# EasyEDA_Schema_SourceFile.net
KiCad netlist of a schematic drawn in EasyEDA
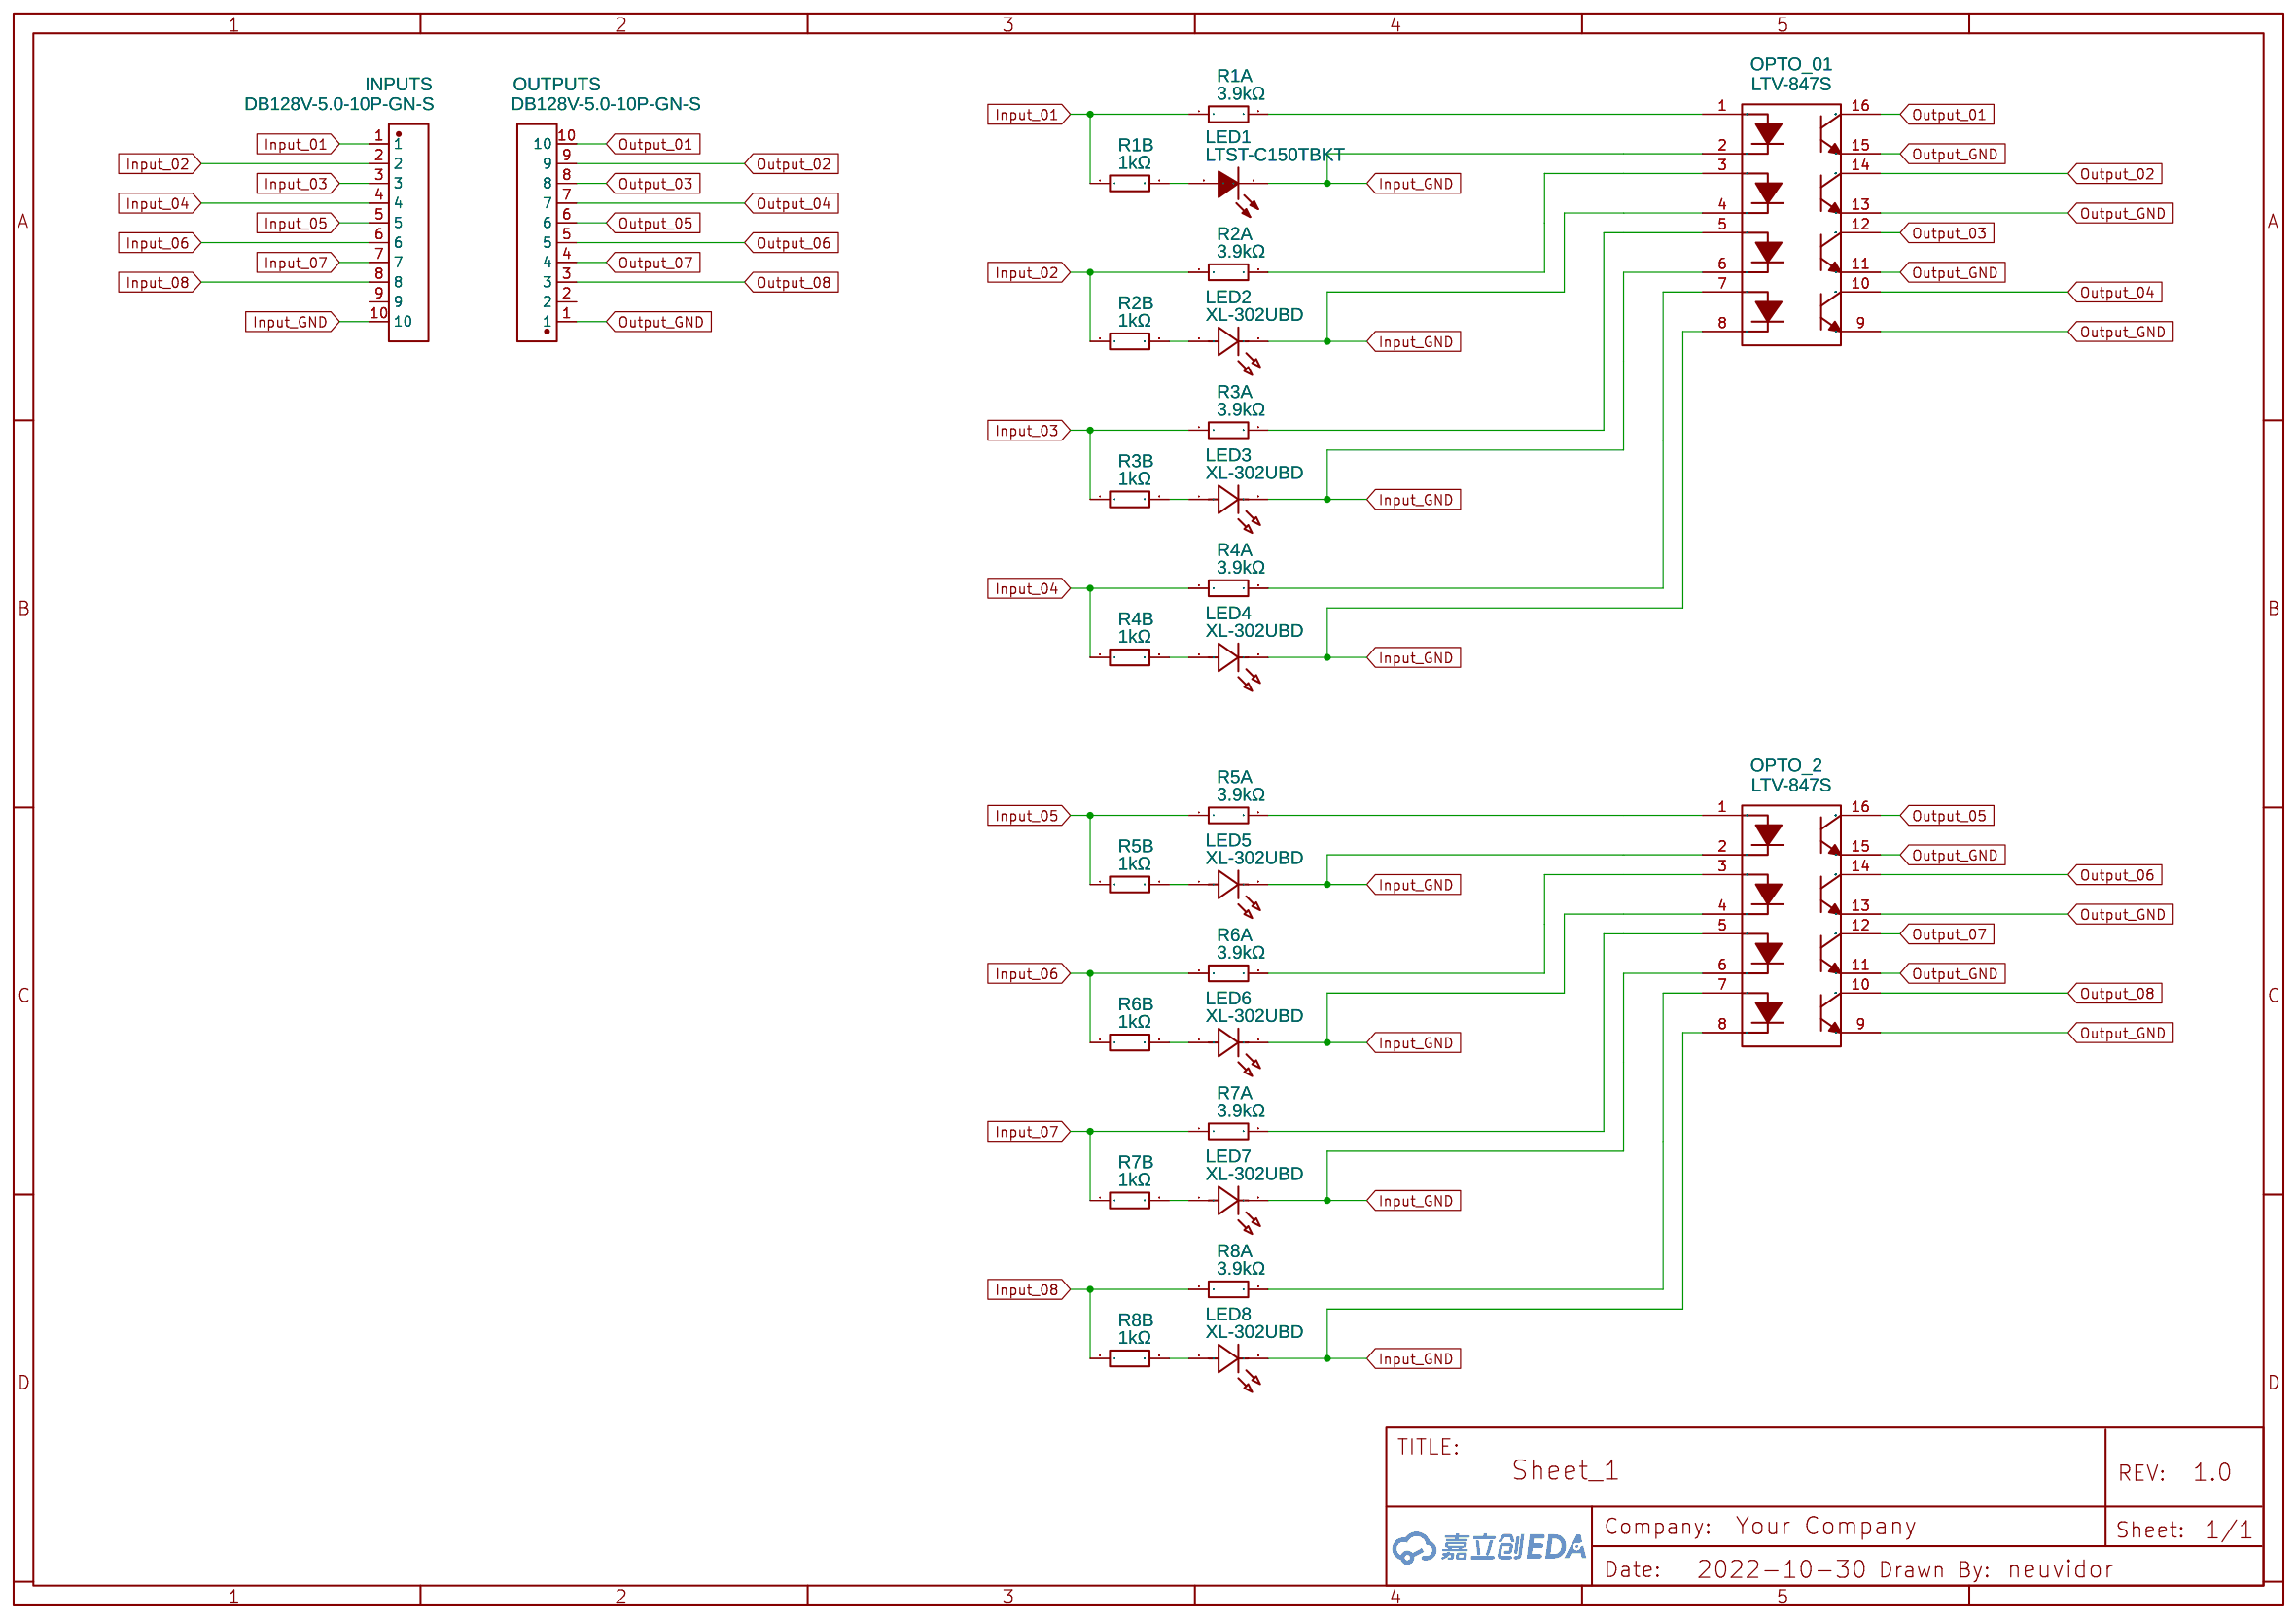
[diagram p0: schematic sheet]

(export (version "E")
  (design (tool "Eeschema 10.0.6"))
  (components
    (comp (ref "INPUTS")
      (value "DB128V-5.0-10P-GN-S")
      (fields (field (name "BOM_Supplier Part") "C725714"))
      (libsource (lib "") (part "DB128V-5.0-10P-GN-S_1"))
    )
    (comp (ref "LED1")
      (value "LTST-C150TBKT")
      (fields (field (name "BOM_Supplier Part") "C125088"))
      (libsource (lib "") (part "LTST-C150TBKT"))
    )
    (comp (ref "LED2")
      (value "XL-302UBD")
      (fields (field (name "BOM_Supplier Part") "C2895474"))
      (libsource (lib "") (part "XL-302UBD"))
    )
    (comp (ref "LED3")
      (value "XL-302UBD")
      (fields (field (name "BOM_Supplier Part") "C2895474"))
      (libsource (lib "") (part "XL-302UBD"))
    )
    (comp (ref "LED4")
      (value "XL-302UBD")
      (fields (field (name "BOM_Supplier Part") "C2895474"))
      (libsource (lib "") (part "XL-302UBD"))
    )
    (comp (ref "LED5")
      (value "XL-302UBD")
      (fields (field (name "BOM_Supplier Part") "C2895474"))
      (libsource (lib "") (part "XL-302UBD"))
    )
    (comp (ref "LED6")
      (value "XL-302UBD")
      (fields (field (name "BOM_Supplier Part") "C2895474"))
      (libsource (lib "") (part "XL-302UBD"))
    )
    (comp (ref "LED7")
      (value "XL-302UBD")
      (fields (field (name "BOM_Supplier Part") "C2895474"))
      (libsource (lib "") (part "XL-302UBD"))
    )
    (comp (ref "LED8")
      (value "XL-302UBD")
      (fields (field (name "BOM_Supplier Part") "C2895474"))
      (libsource (lib "") (part "XL-302UBD"))
    )
    (comp (ref "OPTO_01")
      (value "LTV-847S")
      (fields (field (name "BOM_Supplier Part") "C114599"))
      (libsource (lib "") (part "LTV-847S"))
    )
    (comp (ref "OPTO_2")
      (value "LTV-847S")
      (fields (field (name "BOM_Supplier Part") "C114599"))
      (libsource (lib "") (part "LTV-847S"))
    )
    (comp (ref "OUTPUTS")
      (value "DB128V-5.0-10P-GN-S")
      (fields (field (name "BOM_Supplier Part") "C725714"))
      (libsource (lib "") (part "DB128V-5.0-10P-GN-S"))
    )
    (comp (ref "R1A")
      (value "3.9kΩ")
      (fields
        (field (name "BOM_Manufacturer Part") "AECR1206F3K90K9")
        (field (name "BOM_Supplier Part") "C352079")
      )
      (libsource (lib "") (part "AECR1206F3K90K9_3"))
    )
    (comp (ref "R1B")
      (value "1kΩ")
      (fields
        (field (name "BOM_Manufacturer Part") "PTFR1206B1K00P9")
        (field (name "BOM_Supplier Part") "C351483")
      )
      (libsource (lib "") (part "PTFR1206B1K00P9_1"))
    )
    (comp (ref "R2A")
      (value "3.9kΩ")
      (fields
        (field (name "BOM_Manufacturer Part") "AECR1206F3K90K9")
        (field (name "BOM_Supplier Part") "C352079")
      )
      (libsource (lib "") (part "AECR1206F3K90K9_5"))
    )
    (comp (ref "R2B")
      (value "1kΩ")
      (fields
        (field (name "BOM_Manufacturer Part") "PTFR1206B1K00P9")
        (field (name "BOM_Supplier Part") "C351483")
      )
      (libsource (lib "") (part "PTFR1206B1K00P9_2"))
    )
    (comp (ref "R3A")
      (value "3.9kΩ")
      (fields
        (field (name "BOM_Manufacturer Part") "AECR1206F3K90K9")
        (field (name "BOM_Supplier Part") "C352079")
      )
      (libsource (lib "") (part "AECR1206F3K90K9_2"))
    )
    (comp (ref "R3B")
      (value "1kΩ")
      (fields
        (field (name "BOM_Manufacturer Part") "PTFR1206B1K00P9")
        (field (name "BOM_Supplier Part") "C351483")
      )
      (libsource (lib "") (part "PTFR1206B1K00P9_6"))
    )
    (comp (ref "R4A")
      (value "3.9kΩ")
      (fields
        (field (name "BOM_Manufacturer Part") "AECR1206F3K90K9")
        (field (name "BOM_Supplier Part") "C352079")
      )
      (libsource (lib "") (part "AECR1206F3K90K9"))
    )
    (comp (ref "R4B")
      (value "1kΩ")
      (fields
        (field (name "BOM_Manufacturer Part") "PTFR1206B1K00P9")
        (field (name "BOM_Supplier Part") "C351483")
      )
      (libsource (lib "") (part "PTFR1206B1K00P9_5"))
    )
    (comp (ref "R5A")
      (value "3.9kΩ")
      (fields
        (field (name "BOM_Manufacturer Part") "AECR1206F3K90K9")
        (field (name "BOM_Supplier Part") "C352079")
      )
      (libsource (lib "") (part "AECR1206F3K90K9_7"))
    )
    (comp (ref "R5B")
      (value "1kΩ")
      (fields
        (field (name "BOM_Manufacturer Part") "PTFR1206B1K00P9")
        (field (name "BOM_Supplier Part") "C351483")
      )
      (libsource (lib "") (part "PTFR1206B1K00P9_3"))
    )
    (comp (ref "R6A")
      (value "3.9kΩ")
      (fields
        (field (name "BOM_Manufacturer Part") "AECR1206F3K90K9")
        (field (name "BOM_Supplier Part") "C352079")
      )
      (libsource (lib "") (part "AECR1206F3K90K9_1"))
    )
    (comp (ref "R6B")
      (value "1kΩ")
      (fields
        (field (name "BOM_Manufacturer Part") "PTFR1206B1K00P9")
        (field (name "BOM_Supplier Part") "C351483")
      )
      (libsource (lib "") (part "PTFR1206B1K00P9_7"))
    )
    (comp (ref "R7A")
      (value "3.9kΩ")
      (fields
        (field (name "BOM_Manufacturer Part") "AECR1206F3K90K9")
        (field (name "BOM_Supplier Part") "C352079")
      )
      (libsource (lib "") (part "AECR1206F3K90K9_4"))
    )
    (comp (ref "R7B")
      (value "1kΩ")
      (fields
        (field (name "BOM_Manufacturer Part") "PTFR1206B1K00P9")
        (field (name "BOM_Supplier Part") "C351483")
      )
      (libsource (lib "") (part "PTFR1206B1K00P9"))
    )
    (comp (ref "R8A")
      (value "3.9kΩ")
      (fields
        (field (name "BOM_Manufacturer Part") "AECR1206F3K90K9")
        (field (name "BOM_Supplier Part") "C352079")
      )
      (libsource (lib "") (part "AECR1206F3K90K9_6"))
    )
    (comp (ref "R8B")
      (value "1kΩ")
      (fields
        (field (name "BOM_Manufacturer Part") "PTFR1206B1K00P9")
        (field (name "BOM_Supplier Part") "C351483")
      )
      (libsource (lib "") (part "PTFR1206B1K00P9_4"))
    )
  )
  (nets
    (net (code "1") (name "Input_01") (class "Default")
      (node (ref "INPUTS") (pin "1") (pinfunction "1_1") (pintype "unspecified"))
      (node (ref "R1A") (pin "1") (pinfunction "1_1") (pintype "unspecified"))
      (node (ref "R1B") (pin "1") (pinfunction "1_1") (pintype "unspecified"))
    )
    (net (code "2") (name "Input_02") (class "Default")
      (node (ref "INPUTS") (pin "2") (pinfunction "2_2") (pintype "unspecified"))
      (node (ref "R2A") (pin "1") (pinfunction "1_1") (pintype "unspecified"))
      (node (ref "R2B") (pin "1") (pinfunction "1_1") (pintype "unspecified"))
    )
    (net (code "3") (name "Input_03") (class "Default")
      (node (ref "INPUTS") (pin "3") (pinfunction "3_3") (pintype "unspecified"))
      (node (ref "R3A") (pin "1") (pinfunction "1_1") (pintype "unspecified"))
      (node (ref "R3B") (pin "1") (pinfunction "1_1") (pintype "unspecified"))
    )
    (net (code "4") (name "Input_04") (class "Default")
      (node (ref "INPUTS") (pin "4") (pinfunction "4_4") (pintype "unspecified"))
      (node (ref "R4A") (pin "1") (pinfunction "1_1") (pintype "unspecified"))
      (node (ref "R4B") (pin "1") (pinfunction "1_1") (pintype "unspecified"))
    )
    (net (code "5") (name "Input_05") (class "Default")
      (node (ref "INPUTS") (pin "5") (pinfunction "5_5") (pintype "unspecified"))
      (node (ref "R5A") (pin "1") (pinfunction "1_1") (pintype "unspecified"))
      (node (ref "R5B") (pin "1") (pinfunction "1_1") (pintype "unspecified"))
    )
    (net (code "6") (name "Input_06") (class "Default")
      (node (ref "INPUTS") (pin "6") (pinfunction "6_6") (pintype "unspecified"))
      (node (ref "R6A") (pin "1") (pinfunction "1_1") (pintype "unspecified"))
      (node (ref "R6B") (pin "1") (pinfunction "1_1") (pintype "unspecified"))
    )
    (net (code "7") (name "Input_07") (class "Default")
      (node (ref "INPUTS") (pin "7") (pinfunction "7_7") (pintype "unspecified"))
      (node (ref "R7A") (pin "1") (pinfunction "1_1") (pintype "unspecified"))
      (node (ref "R7B") (pin "1") (pinfunction "1_1") (pintype "unspecified"))
    )
    (net (code "8") (name "Input_08") (class "Default")
      (node (ref "INPUTS") (pin "8") (pinfunction "8_8") (pintype "unspecified"))
      (node (ref "R8A") (pin "1") (pinfunction "1_1") (pintype "unspecified"))
      (node (ref "R8B") (pin "1") (pinfunction "1_1") (pintype "unspecified"))
    )
    (net (code "9") (name "Input_GND") (class "Default")
      (node (ref "INPUTS") (pin "10") (pinfunction "10_10") (pintype "unspecified"))
      (node (ref "LED1") (pin "1") (pinfunction "K_1") (pintype "unspecified"))
      (node (ref "LED2") (pin "2") (pinfunction "A_2") (pintype "unspecified"))
      (node (ref "LED3") (pin "2") (pinfunction "A_2") (pintype "unspecified"))
      (node (ref "LED4") (pin "2") (pinfunction "A_2") (pintype "unspecified"))
      (node (ref "LED5") (pin "2") (pinfunction "A_2") (pintype "unspecified"))
      (node (ref "LED6") (pin "2") (pinfunction "A_2") (pintype "unspecified"))
      (node (ref "LED7") (pin "2") (pinfunction "A_2") (pintype "unspecified"))
      (node (ref "LED8") (pin "2") (pinfunction "A_2") (pintype "unspecified"))
      (node (ref "OPTO_01") (pin "2") (pinfunction "CAT1_2") (pintype "unspecified"))
      (node (ref "OPTO_01") (pin "4") (pinfunction "CAT2_4") (pintype "unspecified"))
      (node (ref "OPTO_01") (pin "6") (pinfunction "CAT3_6") (pintype "unspecified"))
      (node (ref "OPTO_01") (pin "8") (pinfunction "CAT4_8") (pintype "unspecified"))
      (node (ref "OPTO_2") (pin "2") (pinfunction "CAT1_2") (pintype "unspecified"))
      (node (ref "OPTO_2") (pin "4") (pinfunction "CAT2_4") (pintype "unspecified"))
      (node (ref "OPTO_2") (pin "6") (pinfunction "CAT3_6") (pintype "unspecified"))
      (node (ref "OPTO_2") (pin "8") (pinfunction "CAT4_8") (pintype "unspecified"))
    )
    (net (code "10") (name "Net-(LED1-A)") (class "Default")
      (node (ref "LED1") (pin "2") (pinfunction "A_2") (pintype "unspecified"))
      (node (ref "R1B") (pin "2") (pinfunction "2_2") (pintype "unspecified"))
    )
    (net (code "11") (name "Net-(LED2-K)") (class "Default")
      (node (ref "LED2") (pin "1") (pinfunction "K_1") (pintype "unspecified"))
      (node (ref "R2B") (pin "2") (pinfunction "2_2") (pintype "unspecified"))
    )
    (net (code "12") (name "Net-(LED3-K)") (class "Default")
      (node (ref "LED3") (pin "1") (pinfunction "K_1") (pintype "unspecified"))
      (node (ref "R3B") (pin "2") (pinfunction "2_2") (pintype "unspecified"))
    )
    (net (code "13") (name "Net-(LED4-K)") (class "Default")
      (node (ref "LED4") (pin "1") (pinfunction "K_1") (pintype "unspecified"))
      (node (ref "R4B") (pin "2") (pinfunction "2_2") (pintype "unspecified"))
    )
    (net (code "14") (name "Net-(LED5-K)") (class "Default")
      (node (ref "LED5") (pin "1") (pinfunction "K_1") (pintype "unspecified"))
      (node (ref "R5B") (pin "2") (pinfunction "2_2") (pintype "unspecified"))
    )
    (net (code "15") (name "Net-(LED6-K)") (class "Default")
      (node (ref "LED6") (pin "1") (pinfunction "K_1") (pintype "unspecified"))
      (node (ref "R6B") (pin "2") (pinfunction "2_2") (pintype "unspecified"))
    )
    (net (code "16") (name "Net-(LED7-K)") (class "Default")
      (node (ref "LED7") (pin "1") (pinfunction "K_1") (pintype "unspecified"))
      (node (ref "R7B") (pin "2") (pinfunction "2_2") (pintype "unspecified"))
    )
    (net (code "17") (name "Net-(LED8-K)") (class "Default")
      (node (ref "LED8") (pin "1") (pinfunction "K_1") (pintype "unspecified"))
      (node (ref "R8B") (pin "2") (pinfunction "2_2") (pintype "unspecified"))
    )
    (net (code "18") (name "Net-(OPTO_01-AN1)") (class "Default")
      (node (ref "OPTO_01") (pin "1") (pinfunction "AN1_1") (pintype "unspecified"))
      (node (ref "R1A") (pin "2") (pinfunction "2_2") (pintype "unspecified"))
    )
    (net (code "19") (name "Net-(OPTO_01-AN2)") (class "Default")
      (node (ref "OPTO_01") (pin "3") (pinfunction "AN2_3") (pintype "unspecified"))
      (node (ref "R2A") (pin "2") (pinfunction "2_2") (pintype "unspecified"))
    )
    (net (code "20") (name "Net-(OPTO_01-AN3)") (class "Default")
      (node (ref "OPTO_01") (pin "5") (pinfunction "AN3_5") (pintype "unspecified"))
      (node (ref "R3A") (pin "2") (pinfunction "2_2") (pintype "unspecified"))
    )
    (net (code "21") (name "Net-(OPTO_01-AN4)") (class "Default")
      (node (ref "OPTO_01") (pin "7") (pinfunction "AN4_7") (pintype "unspecified"))
      (node (ref "R4A") (pin "2") (pinfunction "2_2") (pintype "unspecified"))
    )
    (net (code "22") (name "Net-(OPTO_2-AN1)") (class "Default")
      (node (ref "OPTO_2") (pin "1") (pinfunction "AN1_1") (pintype "unspecified"))
      (node (ref "R5A") (pin "2") (pinfunction "2_2") (pintype "unspecified"))
    )
    (net (code "23") (name "Net-(OPTO_2-AN2)") (class "Default")
      (node (ref "OPTO_2") (pin "3") (pinfunction "AN2_3") (pintype "unspecified"))
      (node (ref "R6A") (pin "2") (pinfunction "2_2") (pintype "unspecified"))
    )
    (net (code "24") (name "Net-(OPTO_2-AN3)") (class "Default")
      (node (ref "OPTO_2") (pin "5") (pinfunction "AN3_5") (pintype "unspecified"))
      (node (ref "R7A") (pin "2") (pinfunction "2_2") (pintype "unspecified"))
    )
    (net (code "25") (name "Net-(OPTO_2-AN4)") (class "Default")
      (node (ref "OPTO_2") (pin "7") (pinfunction "AN4_7") (pintype "unspecified"))
      (node (ref "R8A") (pin "2") (pinfunction "2_2") (pintype "unspecified"))
    )
    (net (code "26") (name "Output_01") (class "Default")
      (node (ref "OPTO_01") (pin "16") (pinfunction "COL1_16") (pintype "unspecified"))
      (node (ref "OUTPUTS") (pin "10") (pinfunction "10_10") (pintype "unspecified"))
    )
    (net (code "27") (name "Output_02") (class "Default")
      (node (ref "OPTO_01") (pin "14") (pinfunction "COL2_14") (pintype "unspecified"))
      (node (ref "OUTPUTS") (pin "9") (pinfunction "9_9") (pintype "unspecified"))
    )
    (net (code "28") (name "Output_03") (class "Default")
      (node (ref "OPTO_01") (pin "12") (pinfunction "COL3_12") (pintype "unspecified"))
      (node (ref "OUTPUTS") (pin "8") (pinfunction "8_8") (pintype "unspecified"))
    )
    (net (code "29") (name "Output_04") (class "Default")
      (node (ref "OPTO_01") (pin "10") (pinfunction "COL4_10") (pintype "unspecified"))
      (node (ref "OUTPUTS") (pin "7") (pinfunction "7_7") (pintype "unspecified"))
    )
    (net (code "30") (name "Output_05") (class "Default")
      (node (ref "OPTO_2") (pin "16") (pinfunction "COL1_16") (pintype "unspecified"))
      (node (ref "OUTPUTS") (pin "6") (pinfunction "6_6") (pintype "unspecified"))
    )
    (net (code "31") (name "Output_06") (class "Default")
      (node (ref "OPTO_2") (pin "14") (pinfunction "COL2_14") (pintype "unspecified"))
      (node (ref "OUTPUTS") (pin "5") (pinfunction "5_5") (pintype "unspecified"))
    )
    (net (code "32") (name "Output_07") (class "Default")
      (node (ref "OPTO_2") (pin "12") (pinfunction "COL3_12") (pintype "unspecified"))
      (node (ref "OUTPUTS") (pin "4") (pinfunction "4_4") (pintype "unspecified"))
    )
    (net (code "33") (name "Output_08") (class "Default")
      (node (ref "OPTO_2") (pin "10") (pinfunction "COL4_10") (pintype "unspecified"))
      (node (ref "OUTPUTS") (pin "3") (pinfunction "3_3") (pintype "unspecified"))
    )
    (net (code "34") (name "Output_GND") (class "Default")
      (node (ref "OPTO_01") (pin "11") (pinfunction "EM3_11") (pintype "unspecified"))
      (node (ref "OPTO_01") (pin "13") (pinfunction "EM2_13") (pintype "unspecified"))
      (node (ref "OPTO_01") (pin "15") (pinfunction "EM1_15") (pintype "unspecified"))
      (node (ref "OPTO_01") (pin "9") (pinfunction "EM4_9") (pintype "unspecified"))
      (node (ref "OPTO_2") (pin "11") (pinfunction "EM3_11") (pintype "unspecified"))
      (node (ref "OPTO_2") (pin "13") (pinfunction "EM2_13") (pintype "unspecified"))
      (node (ref "OPTO_2") (pin "15") (pinfunction "EM1_15") (pintype "unspecified"))
      (node (ref "OPTO_2") (pin "9") (pinfunction "EM4_9") (pintype "unspecified"))
      (node (ref "OUTPUTS") (pin "1") (pinfunction "1_1") (pintype "unspecified"))
    )
    (net (code "35") (name "unconnected-(INPUTS-Pad9)") (class "Default")
      (node (ref "INPUTS") (pin "9") (pinfunction "9_9") (pintype "unspecified"))
    )
    (net (code "36") (name "unconnected-(OUTPUTS-Pad2)") (class "Default")
      (node (ref "OUTPUTS") (pin "2") (pinfunction "2_2") (pintype "unspecified"))
    )
  )
)
